# POWER.net
KiCad netlist of a schematic drawn in Altium Designer
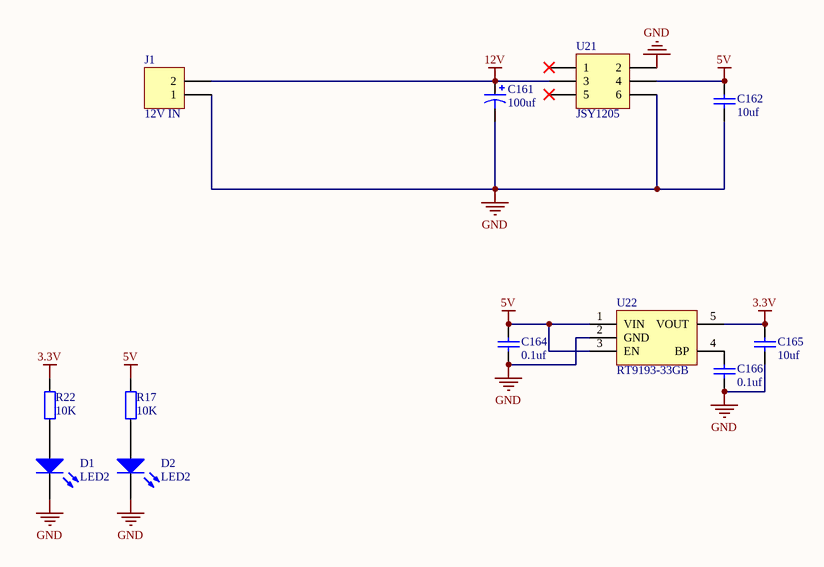
[diagram p0: POWER.SchDoc]

(export (version "E")
  (design (tool "Eeschema 10.0.6"))
  (components
    (comp (ref "C161")
      (value "100uf")
      (footprint "7343C")
      (description "Polarized Capacitor (Radial)")
      (fields (field (name "PUBLISHER") "Altium Limited"))
      (libsource (lib "Miscellaneous Devices") (part "Cap Pol1"))
    )
    (comp (ref "C162")
      (value "10uf")
      (footprint "0805C")
      (description "Capacitor")
      (fields (field (name "PUBLISHER") "Altium Limited"))
      (libsource (lib "Miscellaneous Devices") (part "Cap"))
    )
    (comp (ref "C164")
      (value "0.1uf")
      (footprint "0805C")
      (description "capacitor")
      (fields (field (name "PUBLISHER") "Altium Limited"))
      (libsource (lib "Miscellaneous Devices") (part "Cap"))
    )
    (comp (ref "C165")
      (value "10uf")
      (footprint "0805C")
      (description "Capacitor")
      (fields (field (name "PUBLISHER") "Altium Limited"))
      (libsource (lib "Miscellaneous Devices") (part "Cap"))
    )
    (comp (ref "C166")
      (value "0.1uf")
      (footprint "0805C")
      (description "Capacitor")
      (fields (field (name "PUBLISHER") "Altium Limited"))
      (libsource (lib "Miscellaneous Devices") (part "Cap"))
    )
    (comp (ref "D1")
      (value "LED2")
      (footprint "LED-0805")
      (description "Typical RED, GREEN, YELLOW, AMBER GaAs LED")
      (fields (field (name "PUBLISHER") "Altium Limited"))
      (libsource (lib "Miscellaneous Devices") (part "LED2"))
    )
    (comp (ref "D2")
      (value "LED2")
      (footprint "LED-0805")
      (description "Typical RED, GREEN, YELLOW, AMBER GaAs LED")
      (fields (field (name "PUBLISHER") "Altium Limited"))
      (libsource (lib "Miscellaneous Devices") (part "LED2"))
    )
    (comp (ref "J1")
      (value "12V IN")
      (footprint "VH3.96*2")
      (description "Header, 2-Pin")
      (fields (field (name "PUBLISHER") "Altium Limited"))
      (libsource (lib "Miscellaneous Connectors") (part "Header 2"))
    )
    (comp (ref "R17")
      (value "10K")
      (footprint "0805R")
      (description "Resistor")
      (fields (field (name "PUBLISHER") "Altium Limited"))
      (libsource (lib "Miscellaneous Devices") (part "Res2"))
    )
    (comp (ref "R22")
      (value "10K")
      (footprint "0805R")
      (description "Resistor")
      (fields (field (name "PUBLISHER") "Altium Limited"))
      (libsource (lib "Miscellaneous Devices") (part "Res2"))
    )
    (comp (ref "U21")
      (value "JSY1205")
      (footprint "JSY_1205")
      (description "Header, 3-Pin, Dual row")
      (fields (field (name "PUBLISHER") "Altium Limited"))
      (libsource (lib "Miscellaneous Connectors") (part "Header 3X2"))
    )
    (comp (ref "U22")
      (value "RT9193-33GB")
      (footprint "SOT-23-5L")
      (description "电源芯片")
      (libsource (lib "YS_BDC_V1") (part "RT9193"))
    )
  )
  (nets
    (net (code "1") (name "3.3V") (class "Default")
      (node (ref "C165") (pin "2") (pinfunction "2_2") (pintype "passive"))
      (node (ref "R22") (pin "2") (pinfunction "2_2") (pintype "passive"))
      (node (ref "U22") (pin "5") (pinfunction "VOUT_5") (pintype "passive"))
    )
    (net (code "2") (name "5V") (class "Default")
      (node (ref "C162") (pin "2") (pinfunction "2_2") (pintype "passive"))
      (node (ref "C164") (pin "2") (pinfunction "2_2") (pintype "passive"))
      (node (ref "R17") (pin "2") (pinfunction "2_2") (pintype "passive"))
      (node (ref "U21") (pin "4") (pinfunction "4_4") (pintype "passive"))
      (node (ref "U22") (pin "1") (pinfunction "VIN_1") (pintype "passive"))
      (node (ref "U22") (pin "3") (pinfunction "EN_3") (pintype "passive"))
    )
    (net (code "3") (name "12V") (class "Default")
      (node (ref "C161") (pin "1") (pinfunction "1_1") (pintype "passive"))
      (node (ref "J1") (pin "2") (pinfunction "2_2") (pintype "passive"))
      (node (ref "U21") (pin "3") (pinfunction "3_3") (pintype "passive"))
    )
    (net (code "4") (name "GND") (class "Default")
      (node (ref "C161") (pin "2") (pinfunction "2_2") (pintype "passive"))
      (node (ref "C162") (pin "1") (pinfunction "1_1") (pintype "passive"))
      (node (ref "C164") (pin "1") (pinfunction "1_1") (pintype "passive"))
      (node (ref "C165") (pin "1") (pinfunction "1_1") (pintype "passive"))
      (node (ref "C166") (pin "1") (pinfunction "1_1") (pintype "passive"))
      (node (ref "D1") (pin "2") (pinfunction "K_2") (pintype "passive"))
      (node (ref "D2") (pin "2") (pinfunction "K_2") (pintype "passive"))
      (node (ref "J1") (pin "1") (pinfunction "1_1") (pintype "passive"))
      (node (ref "U21") (pin "2") (pinfunction "2_2") (pintype "passive"))
      (node (ref "U21") (pin "6") (pinfunction "6_6") (pintype "passive"))
      (node (ref "U22") (pin "2") (pinfunction "GND_2") (pintype "passive"))
    )
    (net (code "5") (name "Net-(D1-A)") (class "Default")
      (node (ref "D1") (pin "1") (pinfunction "A_1") (pintype "passive"))
      (node (ref "R22") (pin "1") (pinfunction "1_1") (pintype "passive"))
    )
    (net (code "6") (name "Net-(D2-A)") (class "Default")
      (node (ref "D2") (pin "1") (pinfunction "A_1") (pintype "passive"))
      (node (ref "R17") (pin "1") (pinfunction "1_1") (pintype "passive"))
    )
    (net (code "7") (name "Net-(U22-BP)") (class "Default")
      (node (ref "C166") (pin "2") (pinfunction "2_2") (pintype "passive"))
      (node (ref "U22") (pin "4") (pinfunction "BP_4") (pintype "passive"))
    )
    (net (code "8") (name "unconnected-(U21-Pad1)") (class "Default")
      (node (ref "U21") (pin "1") (pinfunction "1_1") (pintype "passive+no_connect"))
    )
    (net (code "9") (name "unconnected-(U21-Pad5)") (class "Default")
      (node (ref "U21") (pin "5") (pinfunction "5_5") (pintype "passive+no_connect"))
    )
  )
)
